# switch.net
KiCad netlist of a schematic drawn in Altium Designer
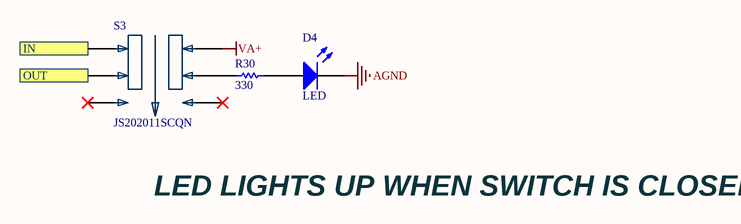
[diagram p0: switch.SchDoc]

(export (version "E")
  (design (tool "Eeschema 10.0.6"))
  (components
    (comp (ref "D4")
      (value "LED")
      (footprint "STD_LED")
      (description "Typical LED")
      (libsource (lib "Arturo_Approved") (part "LNJ037X8ARA"))
    )
    (comp (ref "R30")
      (value "330")
      (footprint "STD_0805_R")
      (description "330 1% 1/3W")
      (libsource (lib "Arturo_Approved") (part "RL1220S-R33-F"))
    )
    (comp (ref "S3")
      (value "JS202011SCQN")
      (footprint "SW_JS202011SCQN")
      (description "Slide Switch DPDT Surface Mount")
      (fields (field (name "DIGI-KEY_PART_NUMBER") "401-2002-1-ND") (field (name "MF") "C&K"))
      (libsource (lib "Arturo_Approved") (part "JS202011SCQN"))
    )
  )
  (nets
    (net (code "1") (name "/IN") (class "Default")
      (node (ref "S3") (pin "1") (pinfunction "1_1") (pintype "passive"))
    )
    (net (code "2") (name "/OUT") (class "Default")
      (node (ref "S3") (pin "2") (pinfunction "2_2") (pintype "passive"))
    )
    (net (code "3") (name "AGND") (class "Default")
      (node (ref "D4") (pin "2") (pinfunction "2_2") (pintype "passive"))
    )
    (net (code "4") (name "Net-(D4-Pad1)") (class "Default")
      (node (ref "D4") (pin "1") (pinfunction "1_1") (pintype "passive"))
      (node (ref "R30") (pin "2") (pinfunction "2_2") (pintype "passive"))
    )
    (net (code "5") (name "Net-(R30-Pad1)") (class "Default")
      (node (ref "R30") (pin "1") (pinfunction "1_1") (pintype "passive"))
      (node (ref "S3") (pin "5") (pinfunction "5_5") (pintype "passive"))
    )
    (net (code "6") (name "VA+") (class "Default")
      (node (ref "S3") (pin "4") (pinfunction "4_4") (pintype "passive"))
    )
    (net (code "7") (name "unconnected-(S3-Pad3)") (class "Default")
      (node (ref "S3") (pin "3") (pinfunction "3_3") (pintype "passive+no_connect"))
    )
    (net (code "8") (name "unconnected-(S3-Pad6)") (class "Default")
      (node (ref "S3") (pin "6") (pinfunction "6_6") (pintype "passive+no_connect"))
    )
  )
)
